# Steering_Converter_ZXBM5210.net
KiCad netlist of a schematic drawn in Altium Designer
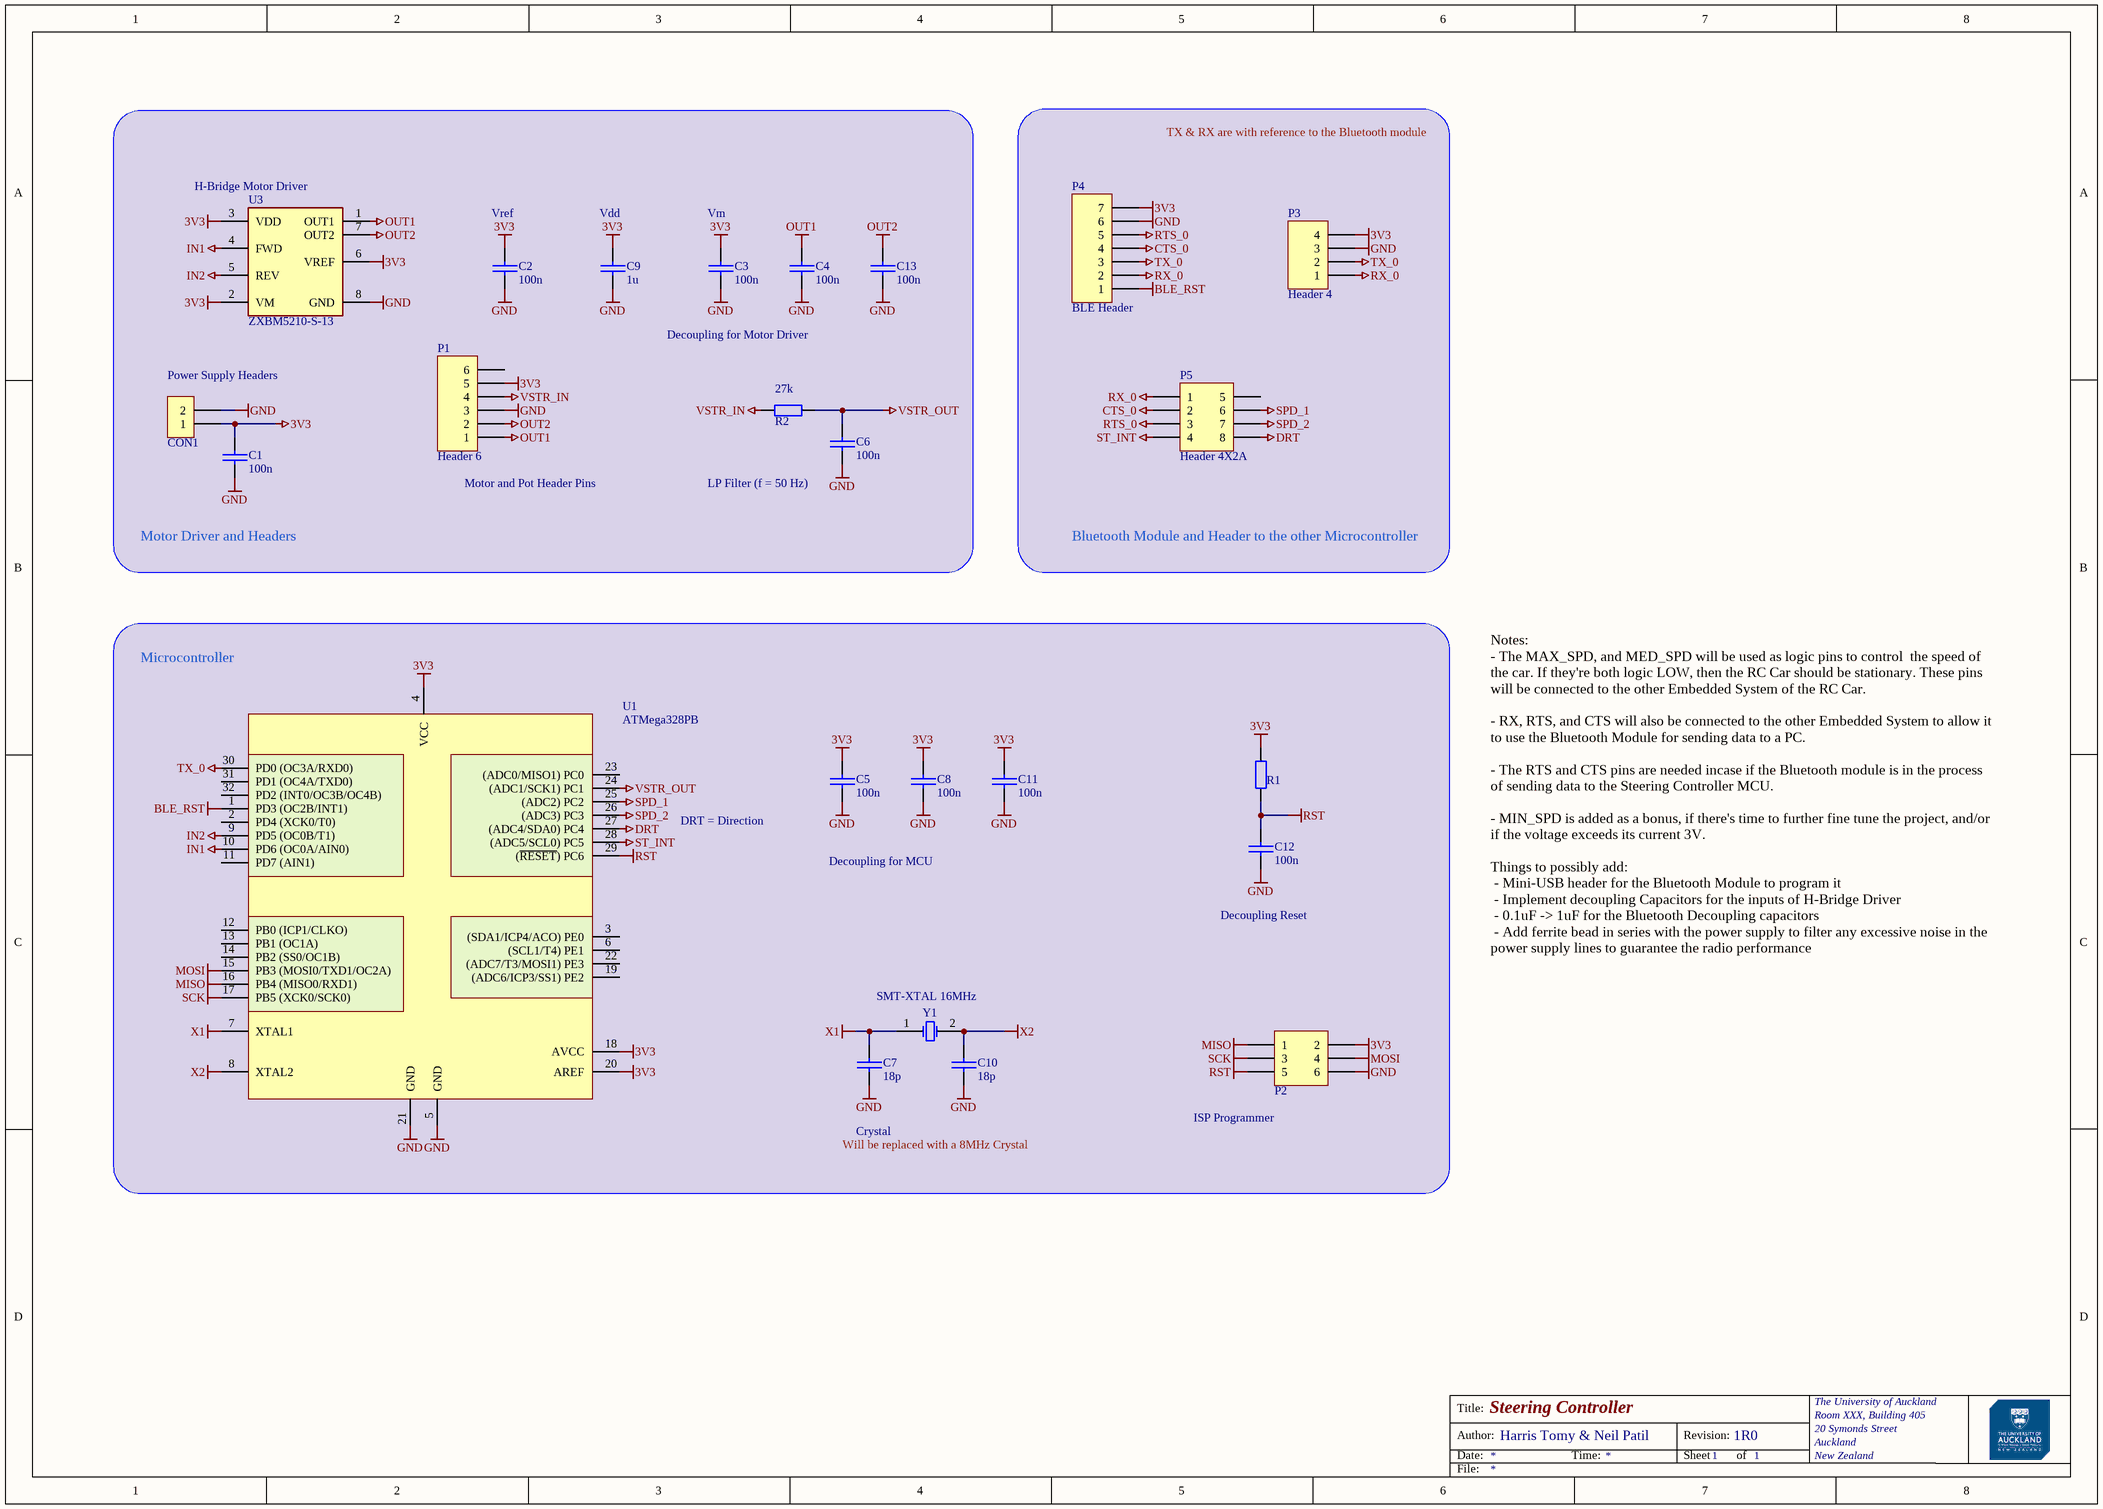
[diagram p0: Steering_Converter_ZXBM5210.SchDoc]

(export (version "E")
  (design (tool "Eeschema 10.0.6"))
  (components
    (comp (ref "C1")
      (value "100n")
      (footprint "C0805")
      (description "CCAP0805")
      (fields (field (name "MPN") "?"))
      (libsource (lib "E209_Lib") (part "CCAP0805"))
    )
    (comp (ref "C2")
      (value "100n")
      (footprint "C0805")
      (description "CCAP0805")
      (fields (field (name "MPN") "?"))
      (libsource (lib "E209_Lib") (part "CCAP0805"))
    )
    (comp (ref "C3")
      (value "100n")
      (footprint "C0805")
      (description "CCAP0805")
      (fields (field (name "MPN") "?"))
      (libsource (lib "E209_Lib") (part "CCAP0805"))
    )
    (comp (ref "C4")
      (value "100n")
      (footprint "C0805")
      (description "CCAP0805")
      (fields (field (name "MPN") "?"))
      (libsource (lib "E209_Lib") (part "CCAP0805"))
    )
    (comp (ref "C5")
      (value "100n")
      (footprint "C0805")
      (description "CCAP0805")
      (fields (field (name "MPN") "?"))
      (libsource (lib "E209_Lib") (part "CCAP0805"))
    )
    (comp (ref "C6")
      (value "100n")
      (footprint "C0805")
      (description "CCAP0805")
      (fields (field (name "MPN") "?"))
      (libsource (lib "E209_Lib") (part "CCAP0805"))
    )
    (comp (ref "C7")
      (value "18p")
      (footprint "C0805")
      (description "CCAP0805")
      (fields (field (name "MPN") "?"))
      (libsource (lib "E209_Lib") (part "CCAP0805"))
    )
    (comp (ref "C8")
      (value "100n")
      (footprint "C0805")
      (description "CCAP0805")
      (fields (field (name "MPN") "?"))
      (libsource (lib "E209_Lib") (part "CCAP0805"))
    )
    (comp (ref "C9")
      (value "1u")
      (footprint "C0805")
      (description "CCAP0805")
      (fields (field (name "MPN") "?"))
      (libsource (lib "E209_Lib") (part "CCAP0805"))
    )
    (comp (ref "C10")
      (value "18p")
      (footprint "C0805")
      (description "CCAP0805")
      (fields (field (name "MPN") "?"))
      (libsource (lib "E209_Lib") (part "CCAP0805"))
    )
    (comp (ref "C11")
      (value "100n")
      (footprint "C0805")
      (description "CCAP0805")
      (fields (field (name "MPN") "?"))
      (libsource (lib "E209_Lib") (part "CCAP0805"))
    )
    (comp (ref "C12")
      (value "100n")
      (footprint "C0805")
      (description "CCAP0805")
      (fields (field (name "MPN") "?"))
      (libsource (lib "E209_Lib") (part "CCAP0805"))
    )
    (comp (ref "C13")
      (value "100n")
      (footprint "C0805")
      (description "CCAP0805")
      (fields (field (name "MPN") "?"))
      (libsource (lib "E209_Lib") (part "CCAP0805"))
    )
    (comp (ref "CON1")
      (value "Header 2X1")
      (footprint "HDR2X1_2P54")
      (libsource (lib "CommonDevices_V1") (part "HDR2X1"))
    )
    (comp (ref "P1")
      (value "Header 6")
      (footprint "HDR1X6")
      (description "Header, 6-Pin")
      (fields (field (name "PUBLISHER") "Altium Limited"))
      (libsource (lib "Miscellaneous Connectors") (part "Header 6"))
    )
    (comp (ref "P2")
      (value "HDR3X2")
      (footprint "HDR2X3_2P54")
      (description "Header, 3-Pin, Dual row")
      (libsource (lib "CommonDevices_V1") (part "HDR3X2"))
    )
    (comp (ref "P3")
      (value "Header 4")
      (footprint "HDR1X4")
      (description "Header, 4-Pin")
      (fields (field (name "PUBLISHER") "Altium Limited"))
      (libsource (lib "Miscellaneous Connectors") (part "Header 4"))
    )
    (comp (ref "P4")
      (value "BLE Header")
      (footprint "HDR1X7")
      (description "Header, 7-Pin")
      (fields (field (name "PUBLISHER") "Altium Limited"))
      (libsource (lib "Miscellaneous Connectors") (part "Header 7"))
    )
    (comp (ref "P5")
      (value "Header 4X2A")
      (footprint "HDR2X4_CEN")
      (description "Header, 4-Pin, Dual row")
      (fields (field (name "PUBLISHER") "Altium Limited"))
      (libsource (lib "Miscellaneous Connectors") (part "Header 4X2A"))
    )
    (comp (ref "R1")
      (value "Resistor 0805")
      (footprint "R0805")
      (description "RES0805")
      (fields (field (name "MPN") "?"))
      (libsource (lib "E209_Lib") (part "RES0805"))
    )
    (comp (ref "R2")
      (value "Resistor 0805")
      (footprint "R0805")
      (description "RES0805")
      (fields (field (name "MPN") "?"))
      (libsource (lib "") (part "RES0805_1"))
    )
    (comp (ref "U1")
      (value "ATMega328PB")
      (footprint "TQFP32")
      (description "IC MCU 8BIT 32KB FLASH 32TQFP")
      (libsource (lib "CommonDevices_V1") (part "ATMega328PB"))
    )
    (comp (ref "U3")
      (value "IC_Diodes_ZXBM5210-S-13_eec")
      (footprint "Diodes_ZXBM5210-S-13_0")
      (description "IC MOTOR DRIVER PWM 8SOIC")
      (fields
        (field (name "PART NUMBER") "ZXBM5210-S-13")
        (field (name "VOLTAGE") "18V")
        (field (name "MANUFACTURER") "Diodes")
      )
      (libsource (lib "ZXBM5210-S-13") (part "IC_Diodes_ZXBM5210-S-13_eec"))
    )
    (comp (ref "Y1")
      (value "SMT-XTAL 16MHz")
      (footprint "HC49-US")
      (description "9C-16.000MAAJ-T crystal 16.0000MHZ 18PF SMD")
      (fields
        (field (name "MANUFACTURER") "TXC CORPORATION")
        (field (name "MANUFACTURER PART NUMBER") "9C-16.000MAAJ-T")
      )
      (libsource (lib "EE209_Library") (part "TXC9C-16_XTAL_SMT"))
    )
  )
  (nets
    (net (code "1") (name "3V3") (class "Default")
      (node (ref "C1") (pin "2") (pinfunction "2_2") (pintype "passive"))
      (node (ref "C11") (pin "2") (pinfunction "2_2") (pintype "passive"))
      (node (ref "C2") (pin "2") (pinfunction "2_2") (pintype "passive"))
      (node (ref "C3") (pin "2") (pinfunction "2_2") (pintype "passive"))
      (node (ref "C5") (pin "2") (pinfunction "2_2") (pintype "passive"))
      (node (ref "C8") (pin "2") (pinfunction "2_2") (pintype "passive"))
      (node (ref "C9") (pin "2") (pinfunction "2_2") (pintype "passive"))
      (node (ref "CON1") (pin "1") (pinfunction "1_1") (pintype "passive"))
      (node (ref "P1") (pin "5") (pinfunction "5_5") (pintype "passive"))
      (node (ref "P2") (pin "2") (pinfunction "2_2") (pintype "passive"))
      (node (ref "P3") (pin "4") (pinfunction "4_4") (pintype "passive"))
      (node (ref "P4") (pin "7") (pinfunction "7_7") (pintype "passive"))
      (node (ref "R1") (pin "2") (pinfunction "2_2") (pintype "passive"))
      (node (ref "U1") (pin "18") (pinfunction "AVCC_18") (pintype "passive"))
      (node (ref "U1") (pin "20") (pinfunction "AREF_20") (pintype "passive"))
      (node (ref "U1") (pin "4") (pinfunction "VCC_4") (pintype "passive"))
      (node (ref "U3") (pin "2") (pinfunction "VM_2") (pintype "passive"))
      (node (ref "U3") (pin "3") (pinfunction "VDD_3") (pintype "passive"))
      (node (ref "U3") (pin "6") (pinfunction "VREF_6") (pintype "passive"))
    )
    (net (code "2") (name "BLE_RST") (class "Default")
      (node (ref "P4") (pin "1") (pinfunction "1_1") (pintype "passive"))
      (node (ref "U1") (pin "1") (pinfunction "PD3_(OC2B/INT1)_1") (pintype "passive"))
    )
    (net (code "3") (name "CTS_0") (class "Default")
      (node (ref "P4") (pin "4") (pinfunction "4_4") (pintype "passive"))
      (node (ref "P5") (pin "2") (pinfunction "2_2") (pintype "passive"))
    )
    (net (code "4") (name "DRT") (class "Default")
      (node (ref "P5") (pin "8") (pinfunction "8_8") (pintype "passive"))
      (node (ref "U1") (pin "27") (pinfunction "(ADC4/SDA0)_PC4_27") (pintype "passive"))
    )
    (net (code "5") (name "GND") (class "Default")
      (node (ref "C1") (pin "1") (pinfunction "1_1") (pintype "passive"))
      (node (ref "C10") (pin "1") (pinfunction "1_1") (pintype "passive"))
      (node (ref "C11") (pin "1") (pinfunction "1_1") (pintype "passive"))
      (node (ref "C12") (pin "1") (pinfunction "1_1") (pintype "passive"))
      (node (ref "C13") (pin "1") (pinfunction "1_1") (pintype "passive"))
      (node (ref "C2") (pin "1") (pinfunction "1_1") (pintype "passive"))
      (node (ref "C3") (pin "1") (pinfunction "1_1") (pintype "passive"))
      (node (ref "C4") (pin "1") (pinfunction "1_1") (pintype "passive"))
      (node (ref "C5") (pin "1") (pinfunction "1_1") (pintype "passive"))
      (node (ref "C6") (pin "1") (pinfunction "1_1") (pintype "passive"))
      (node (ref "C7") (pin "1") (pinfunction "1_1") (pintype "passive"))
      (node (ref "C8") (pin "1") (pinfunction "1_1") (pintype "passive"))
      (node (ref "C9") (pin "1") (pinfunction "1_1") (pintype "passive"))
      (node (ref "CON1") (pin "2") (pinfunction "2_2") (pintype "passive"))
      (node (ref "P1") (pin "3") (pinfunction "3_3") (pintype "passive"))
      (node (ref "P2") (pin "6") (pinfunction "6_6") (pintype "passive"))
      (node (ref "P3") (pin "3") (pinfunction "3_3") (pintype "passive"))
      (node (ref "P4") (pin "6") (pinfunction "6_6") (pintype "passive"))
      (node (ref "U1") (pin "21") (pinfunction "GND_21") (pintype "passive"))
      (node (ref "U1") (pin "5") (pinfunction "GND_5") (pintype "passive"))
      (node (ref "U3") (pin "8") (pinfunction "GND_8") (pintype "passive"))
    )
    (net (code "6") (name "IN1") (class "Default")
      (node (ref "U1") (pin "10") (pinfunction "PD6_(OC0A/AIN0)_10") (pintype "passive"))
      (node (ref "U3") (pin "4") (pinfunction "FWD_4") (pintype "passive"))
    )
    (net (code "7") (name "IN2") (class "Default")
      (node (ref "U1") (pin "9") (pinfunction "PD5_(OC0B/T1)_9") (pintype "passive"))
      (node (ref "U3") (pin "5") (pinfunction "REV_5") (pintype "passive"))
    )
    (net (code "8") (name "MISO") (class "Default")
      (node (ref "P2") (pin "1") (pinfunction "1_1") (pintype "passive"))
      (node (ref "U1") (pin "16") (pinfunction "PB4_(MISO0/RXD1)_16") (pintype "passive"))
    )
    (net (code "9") (name "MOSI") (class "Default")
      (node (ref "P2") (pin "4") (pinfunction "4_4") (pintype "passive"))
      (node (ref "U1") (pin "15") (pinfunction "PB3_(MOSI0/TXD1/OC2A)_15") (pintype "passive"))
    )
    (net (code "10") (name "OUT1") (class "Default")
      (node (ref "C4") (pin "2") (pinfunction "2_2") (pintype "passive"))
      (node (ref "P1") (pin "1") (pinfunction "1_1") (pintype "passive"))
      (node (ref "U3") (pin "1") (pinfunction "OUT1_1") (pintype "passive"))
    )
    (net (code "11") (name "OUT2") (class "Default")
      (node (ref "C13") (pin "2") (pinfunction "2_2") (pintype "passive"))
      (node (ref "P1") (pin "2") (pinfunction "2_2") (pintype "passive"))
      (node (ref "U3") (pin "7") (pinfunction "OUT2_7") (pintype "passive"))
    )
    (net (code "12") (name "RST") (class "Default")
      (node (ref "C12") (pin "2") (pinfunction "2_2") (pintype "passive"))
      (node (ref "P2") (pin "5") (pinfunction "5_5") (pintype "passive"))
      (node (ref "R1") (pin "1") (pinfunction "1_1") (pintype "passive"))
      (node (ref "U1") (pin "29") (pinfunction "(~{RESET})_PC6_29") (pintype "passive"))
    )
    (net (code "13") (name "RTS_0") (class "Default")
      (node (ref "P4") (pin "5") (pinfunction "5_5") (pintype "passive"))
      (node (ref "P5") (pin "3") (pinfunction "3_3") (pintype "passive"))
    )
    (net (code "14") (name "RX_0") (class "Default")
      (node (ref "P3") (pin "1") (pinfunction "1_1") (pintype "passive"))
      (node (ref "P4") (pin "2") (pinfunction "2_2") (pintype "passive"))
      (node (ref "P5") (pin "1") (pinfunction "1_1") (pintype "passive"))
    )
    (net (code "15") (name "SCK") (class "Default")
      (node (ref "P2") (pin "3") (pinfunction "3_3") (pintype "passive"))
      (node (ref "U1") (pin "17") (pinfunction "PB5_(XCK0/SCK0)_17") (pintype "passive"))
    )
    (net (code "16") (name "SPD_1") (class "Default")
      (node (ref "P5") (pin "6") (pinfunction "6_6") (pintype "passive"))
      (node (ref "U1") (pin "25") (pinfunction "(ADC2)_PC2_25") (pintype "passive"))
    )
    (net (code "17") (name "SPD_2") (class "Default")
      (node (ref "P5") (pin "7") (pinfunction "7_7") (pintype "passive"))
      (node (ref "U1") (pin "26") (pinfunction "(ADC3)_PC3_26") (pintype "passive"))
    )
    (net (code "18") (name "ST_INT") (class "Default")
      (node (ref "P5") (pin "4") (pinfunction "4_4") (pintype "passive"))
      (node (ref "U1") (pin "28") (pinfunction "(ADC5/SCL0)_PC5_28") (pintype "passive"))
    )
    (net (code "19") (name "TX_0") (class "Default")
      (node (ref "P3") (pin "2") (pinfunction "2_2") (pintype "passive"))
      (node (ref "P4") (pin "3") (pinfunction "3_3") (pintype "passive"))
      (node (ref "U1") (pin "30") (pinfunction "PD0_(OC3A/RXD0)_30") (pintype "passive"))
    )
    (net (code "20") (name "VSTR_IN") (class "Default")
      (node (ref "P1") (pin "4") (pinfunction "4_4") (pintype "passive"))
      (node (ref "R2") (pin "1") (pinfunction "1_1") (pintype "passive"))
    )
    (net (code "21") (name "VSTR_OUT") (class "Default")
      (node (ref "C6") (pin "2") (pinfunction "2_2") (pintype "passive"))
      (node (ref "R2") (pin "2") (pinfunction "2_2") (pintype "passive"))
      (node (ref "U1") (pin "24") (pinfunction "(ADC1/SCK1)_PC1_24") (pintype "passive"))
    )
    (net (code "22") (name "X1") (class "Default")
      (node (ref "C7") (pin "2") (pinfunction "2_2") (pintype "passive"))
      (node (ref "U1") (pin "7") (pinfunction "XTAL1_7") (pintype "passive"))
      (node (ref "Y1") (pin "1") (pinfunction "OSC1_1") (pintype "passive"))
    )
    (net (code "23") (name "X2") (class "Default")
      (node (ref "C10") (pin "2") (pinfunction "2_2") (pintype "passive"))
      (node (ref "U1") (pin "8") (pinfunction "XTAL2_8") (pintype "passive"))
      (node (ref "Y1") (pin "2") (pinfunction "OSC2_2") (pintype "passive"))
    )
    (net (code "24") (name "unconnected-(P1-Pad6)") (class "Default")
      (node (ref "P1") (pin "6") (pinfunction "6_6") (pintype "passive"))
    )
    (net (code "25") (name "unconnected-(P5-Pad5)") (class "Default")
      (node (ref "P5") (pin "5") (pinfunction "5_5") (pintype "passive"))
    )
    (net (code "26") (name "unconnected-(U1-(ADC0{slash}MISO1)_PC0-Pad23)") (class "Default")
      (node (ref "U1") (pin "23") (pinfunction "(ADC0/MISO1)_PC0_23") (pintype "passive"))
    )
    (net (code "27") (name "unconnected-(U1-(ADC6{slash}ICP3{slash}SS1)_PE2-Pad19)") (class "Default")
      (node (ref "U1") (pin "19") (pinfunction "(ADC6/ICP3/SS1)_PE2_19") (pintype "passive"))
    )
    (net (code "28") (name "unconnected-(U1-(ADC7{slash}T3{slash}MOSI1)_PE3-Pad22)") (class "Default")
      (node (ref "U1") (pin "22") (pinfunction "(ADC7/T3/MOSI1)_PE3_22") (pintype "passive"))
    )
    (net (code "29") (name "unconnected-(U1-(SCL1{slash}T4)_PE1-Pad6)") (class "Default")
      (node (ref "U1") (pin "6") (pinfunction "(SCL1/T4)_PE1_6") (pintype "passive"))
    )
    (net (code "30") (name "unconnected-(U1-(SDA1{slash}ICP4{slash}ACO)_PE0-Pad3)") (class "Default")
      (node (ref "U1") (pin "3") (pinfunction "(SDA1/ICP4/ACO)_PE0_3") (pintype "passive"))
    )
    (net (code "31") (name "unconnected-(U1-PB0_(ICP1{slash}CLKO)-Pad12)") (class "Default")
      (node (ref "U1") (pin "12") (pinfunction "PB0_(ICP1/CLKO)_12") (pintype "passive"))
    )
    (net (code "32") (name "unconnected-(U1-PB1_(OC1A)-Pad13)") (class "Default")
      (node (ref "U1") (pin "13") (pinfunction "PB1_(OC1A)_13") (pintype "passive"))
    )
    (net (code "33") (name "unconnected-(U1-PB2_(SS0{slash}OC1B)-Pad14)") (class "Default")
      (node (ref "U1") (pin "14") (pinfunction "PB2_(SS0/OC1B)_14") (pintype "passive"))
    )
    (net (code "34") (name "unconnected-(U1-PD1_(OC4A{slash}TXD0)-Pad31)") (class "Default")
      (node (ref "U1") (pin "31") (pinfunction "PD1_(OC4A/TXD0)_31") (pintype "passive"))
    )
    (net (code "35") (name "unconnected-(U1-PD2_(INT0{slash}OC3B{slash}OC4B)-Pad32)") (class "Default")
      (node (ref "U1") (pin "32") (pinfunction "PD2_(INT0/OC3B/OC4B)_32") (pintype "passive"))
    )
    (net (code "36") (name "unconnected-(U1-PD4_(XCK0{slash}T0)-Pad2)") (class "Default")
      (node (ref "U1") (pin "2") (pinfunction "PD4_(XCK0/T0)_2") (pintype "passive"))
    )
    (net (code "37") (name "unconnected-(U1-PD7_(AIN1)-Pad11)") (class "Default")
      (node (ref "U1") (pin "11") (pinfunction "PD7_(AIN1)_11") (pintype "passive"))
    )
  )
)
